# Encoder_Fin_-_System.net
KiCad netlist of a schematic drawn in Altium Designer
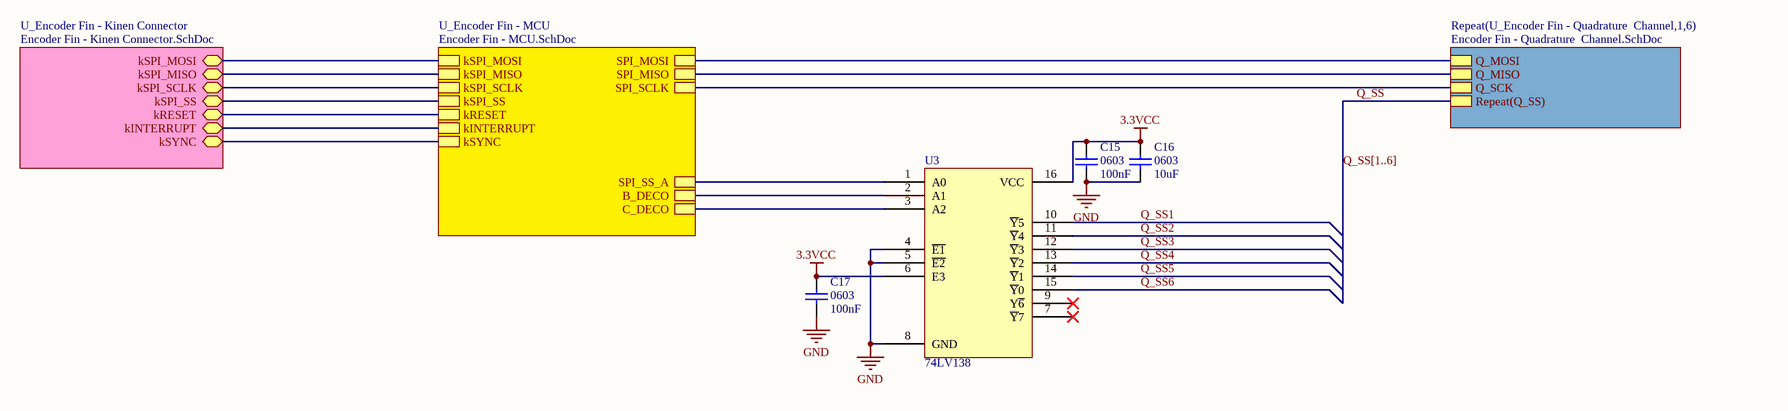
[diagram p0: Encoder Fin - System.SchDoc]

(export (version "E")
  (design (tool "Eeschema 10.0.6"))
  (components
    (comp (ref "C15")
      (value "0603")
      (footprint "1608[0603]")
      (description "Capacitor (Semiconductor SIM Model)")
      (fields (field (name "ALTIUM_VALUE") "100nF") (field (name "PUBLISHER") "Altium Limited"))
      (libsource (lib "Miscellaneous Devices") (part "Cap Semi"))
    )
    (comp (ref "C16")
      (value "0603")
      (footprint "1608[0603]")
      (description "Capacitor (Semiconductor SIM Model)")
      (fields (field (name "ALTIUM_VALUE") "10uF") (field (name "PUBLISHER") "Altium Limited"))
      (libsource (lib "Miscellaneous Devices") (part "Cap Semi"))
    )
    (comp (ref "C17")
      (value "0603")
      (footprint "1608[0603]")
      (description "Capacitor (Semiconductor SIM Model)")
      (fields (field (name "ALTIUM_VALUE") "100nF") (field (name "PUBLISHER") "Altium Limited"))
      (libsource (lib "Miscellaneous Devices") (part "Cap Semi"))
    )
    (comp (ref "U3")
      (value "74LV138")
      (footprint "TSOP65P640X120-16N-74IC")
      (description "74LV138 - 3 to 8 Decoder NXP 3.3v/5v")
      (libsource (lib "Encoder Fin") (part "74LV138 - 3 to 8 Decoder NXP 3.3v/5v"))
    )
  )
  (nets
    (net (code "1") (name "/B_DECO") (class "Default")
      (node (ref "U3") (pin "2") (pinfunction "A1_2") (pintype "passive"))
    )
    (net (code "2") (name "/C_DECO") (class "Default")
      (node (ref "U3") (pin "3") (pinfunction "A2_3") (pintype "passive"))
    )
    (net (code "7") (name "/Q_SS1") (class "Default")
      (node (ref "U3") (pin "10") (pinfunction "~{Y}5_10") (pintype "passive"))
    )
    (net (code "8") (name "/Q_SS2") (class "Default")
      (node (ref "U3") (pin "11") (pinfunction "~{Y}4_11") (pintype "passive"))
    )
    (net (code "9") (name "/Q_SS3") (class "Default")
      (node (ref "U3") (pin "12") (pinfunction "~{Y}3_12") (pintype "passive"))
    )
    (net (code "10") (name "/Q_SS4") (class "Default")
      (node (ref "U3") (pin "13") (pinfunction "~{Y}2_13") (pintype "passive"))
    )
    (net (code "11") (name "/Q_SS5") (class "Default")
      (node (ref "U3") (pin "14") (pinfunction "~{Y}1_14") (pintype "passive"))
    )
    (net (code "12") (name "/Q_SS6") (class "Default")
      (node (ref "U3") (pin "15") (pinfunction "~{Y}0_15") (pintype "passive"))
    )
    (net (code "14") (name "/SPI_SS_A") (class "Default")
      (node (ref "U3") (pin "1") (pinfunction "A0_1") (pintype "passive"))
    )
    (net (code "22") (name "3.3VCC") (class "Default")
      (node (ref "C15") (pin "2") (pinfunction "2_2") (pintype "passive"))
      (node (ref "C16") (pin "2") (pinfunction "2_2") (pintype "passive"))
      (node (ref "C17") (pin "2") (pinfunction "2_2") (pintype "passive"))
      (node (ref "U3") (pin "16") (pinfunction "VCC_16") (pintype "passive"))
      (node (ref "U3") (pin "6") (pinfunction "E3_6") (pintype "passive"))
    )
    (net (code "23") (name "GND") (class "Default")
      (node (ref "C15") (pin "1") (pinfunction "1_1") (pintype "passive"))
      (node (ref "C16") (pin "1") (pinfunction "1_1") (pintype "passive"))
      (node (ref "C17") (pin "1") (pinfunction "1_1") (pintype "passive"))
      (node (ref "U3") (pin "4") (pinfunction "~{E1}_4") (pintype "passive"))
      (node (ref "U3") (pin "5") (pinfunction "~{E2}_5") (pintype "passive"))
      (node (ref "U3") (pin "8") (pinfunction "GND_8") (pintype "passive"))
    )
    (net (code "24") (name "unconnected-(U3-Y~{6}-Pad9)") (class "Default")
      (node (ref "U3") (pin "9") (pinfunction "Y~{6}_9") (pintype "passive+no_connect"))
    )
    (net (code "25") (name "unconnected-(U3-~{Y}7-Pad7)") (class "Default")
      (node (ref "U3") (pin "7") (pinfunction "~{Y}7_7") (pintype "passive+no_connect"))
    )
  )
)
